# xmas_ornament_2019.net
KiCad netlist of a schematic drawn in EAGLE
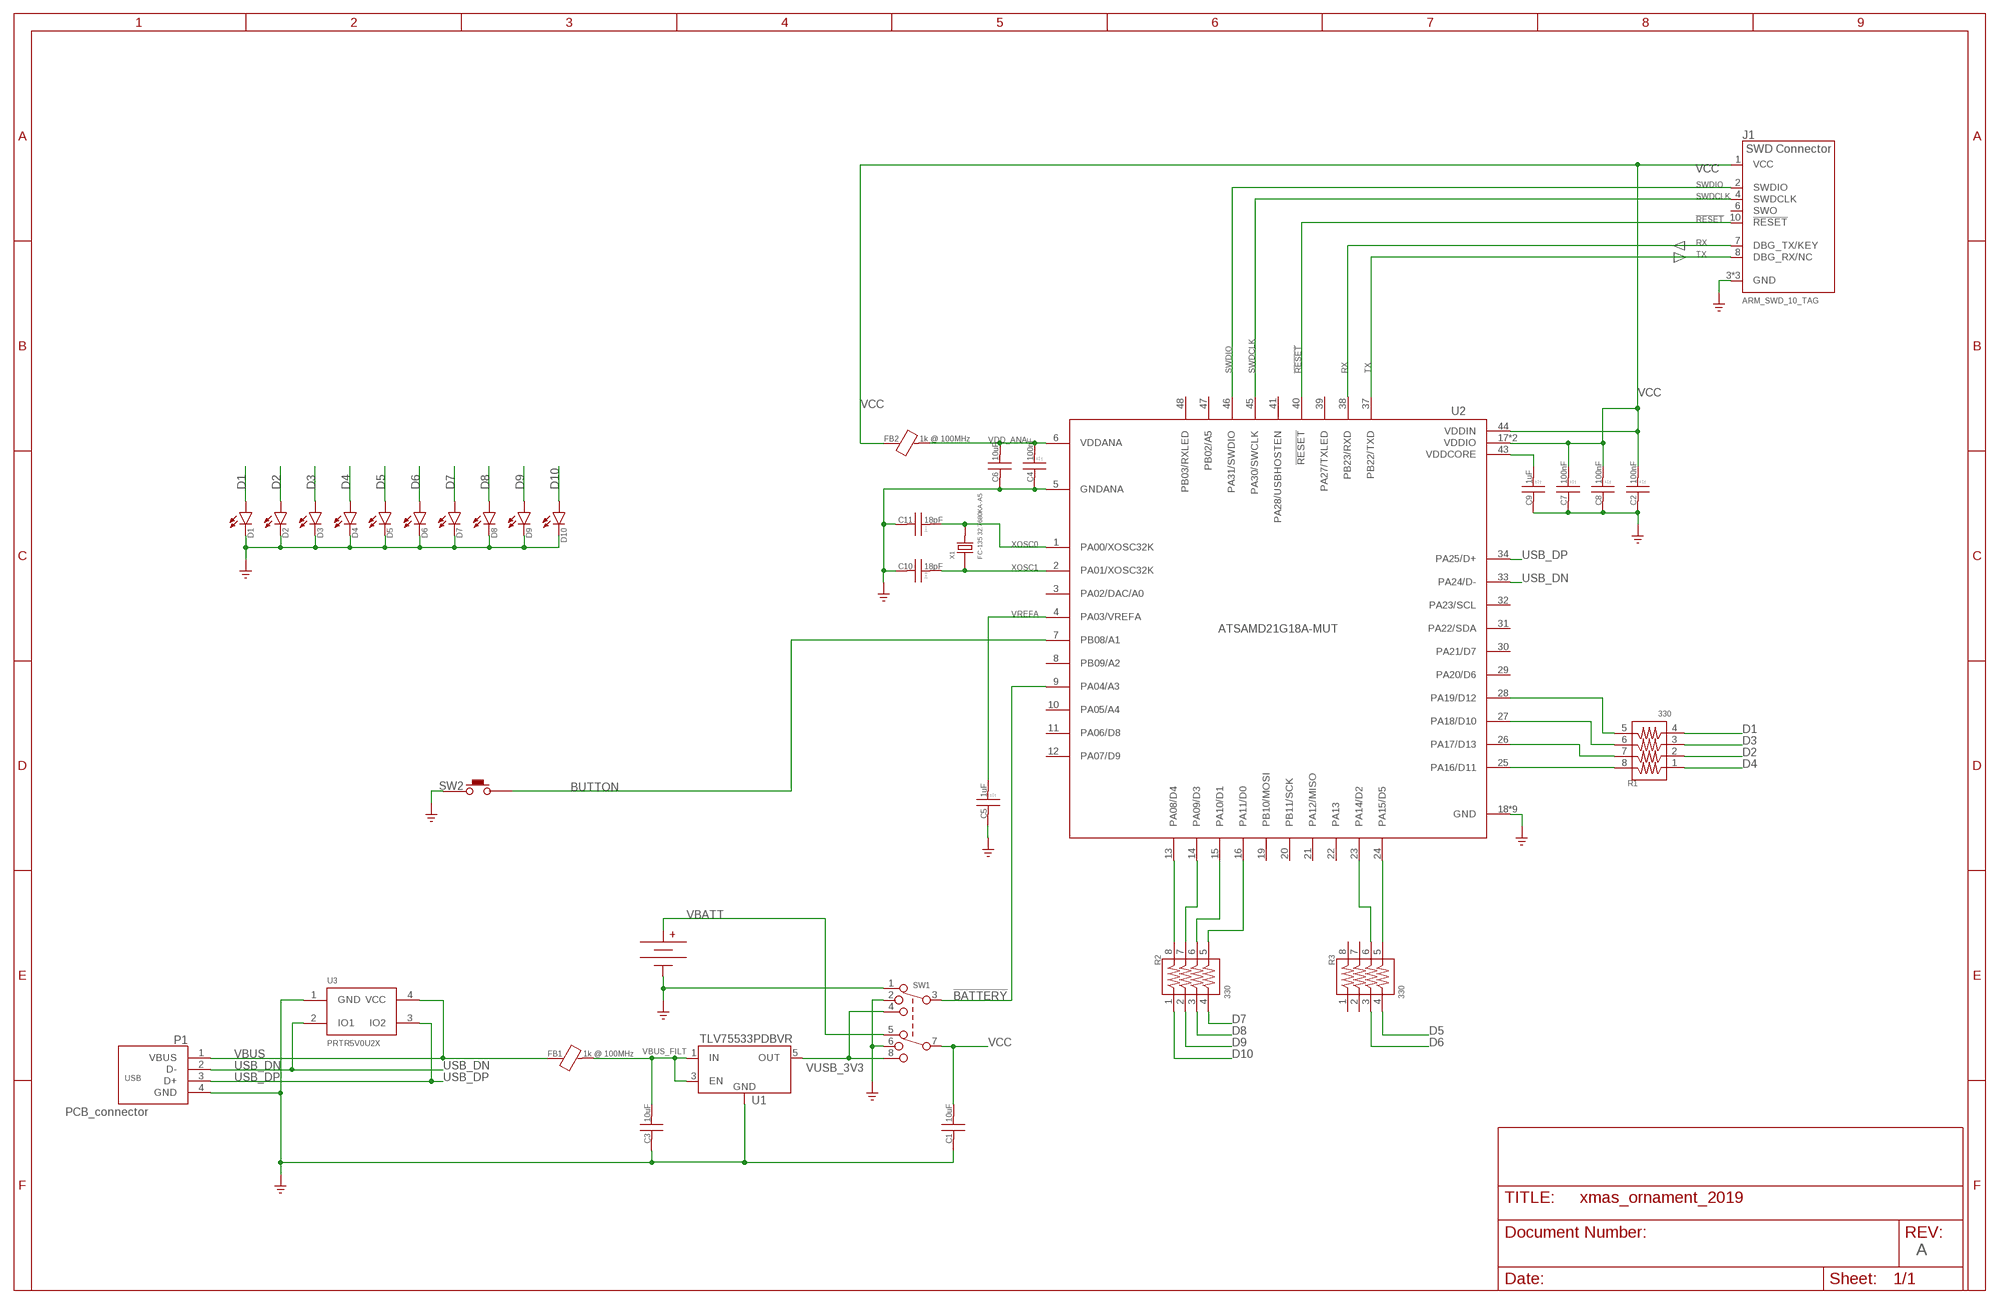
[diagram p0: schematic, sheet 1]

(export (version "E")
  (design (tool "Eeschema 10.0.6"))
  (components
    (comp (ref "C1")
      (value "10uF")
      (footprint "eagle-import:0805")
      (fields
        (field (name "DIELECTRIC") "X7R")
        (field (name "MPN") "JMK212AB7106KGHT")
        (field (name "TOLERANCE") "20%")
        (field (name "VOLTAGE") "6.3V")
      )
      (libsource (lib "eagle-import") (part "CAP_0805"))
    )
    (comp (ref "C2")
      (value "100nF")
      (footprint "eagle-import:0603")
      (fields
        (field (name "DIELECTRIC") "X5R")
        (field (name "MPN") "CC0603KRX7R9BB104")
        (field (name "TOLERANCE") "20%")
        (field (name "VOLTAGE") "50V")
      )
      (libsource (lib "eagle-import") (part "CAP_0603"))
    )
    (comp (ref "C3")
      (value "10uF")
      (footprint "eagle-import:0805")
      (fields
        (field (name "DIELECTRIC") "X7R")
        (field (name "MPN") "JMK212AB7106KGHT")
        (field (name "TOLERANCE") "20%")
        (field (name "VOLTAGE") "6.3V")
      )
      (libsource (lib "eagle-import") (part "CAP_0805"))
    )
    (comp (ref "C4")
      (value "100nF")
      (footprint "eagle-import:0603")
      (fields
        (field (name "DIELECTRIC") "X5R")
        (field (name "MPN") "CC0603KRX7R9BB104")
        (field (name "TOLERANCE") "20%")
        (field (name "VOLTAGE") "50V")
      )
      (libsource (lib "eagle-import") (part "CAP_0603"))
    )
    (comp (ref "C5")
      (value "1uF")
      (footprint "eagle-import:0603")
      (fields
        (field (name "DIELECTRIC") "X5R")
        (field (name "MPN") "CC0603KRX5R6BB105")
        (field (name "TOLERANCE") "20%")
        (field (name "VOLTAGE") "10V")
      )
      (libsource (lib "eagle-import") (part "CAP_0603"))
    )
    (comp (ref "C6")
      (value "10uF")
      (footprint "eagle-import:0805")
      (fields
        (field (name "DIELECTRIC") "X7R")
        (field (name "MPN") "JMK212AB7106KGHT")
        (field (name "TOLERANCE") "20%")
        (field (name "VOLTAGE") "6.3V")
      )
      (libsource (lib "eagle-import") (part "CAP_0805"))
    )
    (comp (ref "C7")
      (value "100nF")
      (footprint "eagle-import:0603")
      (fields
        (field (name "DIELECTRIC") "X5R")
        (field (name "MPN") "CC0603KRX7R9BB104")
        (field (name "TOLERANCE") "20%")
        (field (name "VOLTAGE") "50V")
      )
      (libsource (lib "eagle-import") (part "CAP_0603"))
    )
    (comp (ref "C8")
      (value "100nF")
      (footprint "eagle-import:0603")
      (fields
        (field (name "DIELECTRIC") "X5R")
        (field (name "MPN") "CC0603KRX7R9BB104")
        (field (name "TOLERANCE") "20%")
        (field (name "VOLTAGE") "50V")
      )
      (libsource (lib "eagle-import") (part "CAP_0603"))
    )
    (comp (ref "C9")
      (value "1uF")
      (footprint "eagle-import:0603")
      (fields
        (field (name "DIELECTRIC") "X5R")
        (field (name "MPN") "CC0603KRX5R6BB105")
        (field (name "TOLERANCE") "20%")
        (field (name "VOLTAGE") "10V")
      )
      (libsource (lib "eagle-import") (part "CAP_0603"))
    )
    (comp (ref "C10")
      (value "18pF")
      (footprint "eagle-import:0603")
      (fields
        (field (name "DIELECTRIC") "C0G")
        (field (name "MPN") "GRM1885C1H220JA01D")
        (field (name "TOLERANCE") "5%")
        (field (name "VOLTAGE") "50V")
      )
      (libsource (lib "eagle-import") (part "CAP_0603"))
    )
    (comp (ref "C11")
      (value "18pF")
      (footprint "eagle-import:0603")
      (fields
        (field (name "DIELECTRIC") "C0G")
        (field (name "MPN") "GRM1885C1H220JA01D")
        (field (name "TOLERANCE") "5%")
        (field (name "VOLTAGE") "50V")
      )
      (libsource (lib "eagle-import") (part "CAP_0603"))
    )
    (comp (ref "D1")
      (value "APT2012LSYCK/J3-PRV")
      (footprint "eagle-import:LED_0805_BREV")
      (libsource (lib "eagle-import") (part "LED0805_BREV"))
    )
    (comp (ref "D2")
      (value "APT2012LSYCK/J3-PRV")
      (footprint "eagle-import:LED_0805_BREV")
      (libsource (lib "eagle-import") (part "LED0805_BREV"))
    )
    (comp (ref "D3")
      (value "APT2012LSYCK/J3-PRV")
      (footprint "eagle-import:LED_0805_BREV")
      (libsource (lib "eagle-import") (part "LED0805_BREV"))
    )
    (comp (ref "D4")
      (value "APT2012LSYCK/J3-PRV")
      (footprint "eagle-import:LED_0805_BREV")
      (libsource (lib "eagle-import") (part "LED0805_BREV"))
    )
    (comp (ref "D5")
      (value "APT2012LSYCK/J3-PRV")
      (footprint "eagle-import:LED_0805_BREV")
      (libsource (lib "eagle-import") (part "LED0805_BREV"))
    )
    (comp (ref "D6")
      (value "APT2012LSYCK/J3-PRV")
      (footprint "eagle-import:LED_0805_BREV")
      (libsource (lib "eagle-import") (part "LED0805_BREV"))
    )
    (comp (ref "D7")
      (value "APT2012LSYCK/J3-PRV")
      (footprint "eagle-import:LED_0805_BREV")
      (libsource (lib "eagle-import") (part "LED0805_BREV"))
    )
    (comp (ref "D8")
      (value "APT2012LSYCK/J3-PRV")
      (footprint "eagle-import:LED_0805_BREV")
      (libsource (lib "eagle-import") (part "LED0805_BREV"))
    )
    (comp (ref "D9")
      (value "APT2012LSYCK/J3-PRV")
      (footprint "eagle-import:LED_0805_BREV")
      (libsource (lib "eagle-import") (part "LED0805_BREV"))
    )
    (comp (ref "D10")
      (value "APT2012LSYCK/J3-PRV")
      (footprint "eagle-import:LED_0805_BREV")
      (libsource (lib "eagle-import") (part "LED0805_BREV"))
    )
    (comp (ref "FB1")
      (value "1k @ 100MHz")
      (footprint "eagle-import:0603")
      (fields (field (name "MPN") "742792663"))
      (libsource (lib "eagle-import") (part "FERRITE_BEAD_0603"))
    )
    (comp (ref "FB2")
      (value "1k @ 100MHz")
      (footprint "eagle-import:0603")
      (fields (field (name "MPN") "742792663"))
      (libsource (lib "eagle-import") (part "FERRITE_BEAD_0603"))
    )
    (comp (ref "J1")
      (value "ARM_SWD_10_TAG")
      (footprint "eagle-import:TC2050-IDC-NL")
      (libsource (lib "eagle-import") (part "ARM_SWD_10_TAG"))
    )
    (comp (ref "J2")
      (value "BU2450-SM-JJ-GTR")
      (footprint "eagle-import:BU2450SM-JJ-GTR")
      (libsource (lib "eagle-import") (part "BATTERY_BU2450SM-JJ-G"))
    )
    (comp (ref "P1")
      (value "PCB_connector")
      (footprint "eagle-import:USB-A_PCB")
      (libsource (lib "eagle-import") (part "USB-4-PCB-A"))
    )
    (comp (ref "R1")
      (value "330")
      (footprint "eagle-import:1206X4")
      (fields (field (name "MPN") "EXB-38V331JV") (field (name "TOLERANCE") "5%"))
      (libsource (lib "eagle-import") (part "RESISTOR_4_1206"))
    )
    (comp (ref "R2")
      (value "330")
      (footprint "eagle-import:1206X4")
      (fields (field (name "MPN") "EXB-38V331JV") (field (name "TOLERANCE") "5%"))
      (libsource (lib "eagle-import") (part "RESISTOR_4_1206"))
    )
    (comp (ref "R3")
      (value "330")
      (footprint "eagle-import:1206X4")
      (fields (field (name "MPN") "EXB-38V331JV") (field (name "TOLERANCE") "5%"))
      (libsource (lib "eagle-import") (part "RESISTOR_4_1206"))
    )
    (comp (ref "SW1")
      (value "JS203011SCQN")
      (footprint "eagle-import:JS203011SCQN")
      (libsource (lib "eagle-import") (part "SWITCH-DP3T_JS203011SCQN"))
    )
    (comp (ref "SW2")
      (value "PTS645SM43SMTR92 LFS")
      (footprint "eagle-import:SWITCH_6MM")
      (libsource (lib "eagle-import") (part "SWITCH-SPST-NO"))
    )
    (comp (ref "U1")
      (value "TLV75533PDBVR")
      (footprint "eagle-import:SOT23-5")
      (libsource (lib "eagle-import") (part "VREG_FIXED+_ENTPS70960DBV"))
    )
    (comp (ref "U2")
      (value "ATSAMD21G18A-MUT")
      (footprint "eagle-import:QFN-48_GND")
      (libsource (lib "eagle-import") (part "SAMD21G18A-MUT"))
    )
    (comp (ref "U3")
      (value "PRTR5V0U2X")
      (footprint "eagle-import:SOT143B")
      (fields (field (name "MPN") "PRTR5V0U2X,215"))
      (libsource (lib "eagle-import") (part "PRTR5V0U2X"))
    )
    (comp (ref "X1")
      (value "FC-135 32.7680KA-A5")
      (footprint "eagle-import:XTAL_3.2X1.5")
      (libsource (lib "eagle-import") (part "XTAL-2_3.2X1.5"))
    )
  )
  (nets
    (net (code "1") (name "/BUTTON") (class "Default")
      (node (ref "SW2") (pin "1") (pinfunction "P$1_1") (pintype "bidirectional"))
      (node (ref "SW2") (pin "2") (pinfunction "P$1_2") (pintype "bidirectional"))
      (node (ref "U2") (pin "7") (pinfunction "PB08/A1_7") (pintype "bidirectional"))
    )
    (net (code "2") (name "/D1") (class "Default")
      (node (ref "D1") (pin "A") (pinfunction "A_A") (pintype "passive"))
      (node (ref "R1") (pin "4") (pinfunction "4A_4") (pintype "bidirectional"))
    )
    (net (code "3") (name "/D2") (class "Default")
      (node (ref "D2") (pin "A") (pinfunction "A_A") (pintype "passive"))
      (node (ref "R1") (pin "2") (pinfunction "2A_2") (pintype "bidirectional"))
    )
    (net (code "4") (name "/D3") (class "Default")
      (node (ref "D3") (pin "A") (pinfunction "A_A") (pintype "passive"))
      (node (ref "R1") (pin "3") (pinfunction "3A_3") (pintype "bidirectional"))
    )
    (net (code "5") (name "/D4") (class "Default")
      (node (ref "D4") (pin "A") (pinfunction "A_A") (pintype "passive"))
      (node (ref "R1") (pin "1") (pinfunction "1A_1") (pintype "bidirectional"))
    )
    (net (code "6") (name "/D5") (class "Default")
      (node (ref "D5") (pin "A") (pinfunction "A_A") (pintype "passive"))
      (node (ref "R3") (pin "4") (pinfunction "4A_4") (pintype "bidirectional"))
    )
    (net (code "7") (name "/D6") (class "Default")
      (node (ref "D6") (pin "A") (pinfunction "A_A") (pintype "passive"))
      (node (ref "R3") (pin "3") (pinfunction "3A_3") (pintype "bidirectional"))
    )
    (net (code "8") (name "/D7") (class "Default")
      (node (ref "D7") (pin "A") (pinfunction "A_A") (pintype "passive"))
      (node (ref "R2") (pin "4") (pinfunction "4A_4") (pintype "bidirectional"))
    )
    (net (code "9") (name "/D8") (class "Default")
      (node (ref "D8") (pin "A") (pinfunction "A_A") (pintype "passive"))
      (node (ref "R2") (pin "3") (pinfunction "3A_3") (pintype "bidirectional"))
    )
    (net (code "10") (name "/D9") (class "Default")
      (node (ref "D9") (pin "A") (pinfunction "A_A") (pintype "passive"))
      (node (ref "R2") (pin "2") (pinfunction "2A_2") (pintype "bidirectional"))
    )
    (net (code "11") (name "/D10") (class "Default")
      (node (ref "D10") (pin "A") (pinfunction "A_A") (pintype "passive"))
      (node (ref "R2") (pin "1") (pinfunction "1A_1") (pintype "bidirectional"))
    )
    (net (code "12") (name "/RX") (class "Default")
      (node (ref "J1") (pin "7") (pinfunction "DBG_TX/KEY_7") (pintype "bidirectional"))
      (node (ref "U2") (pin "38") (pinfunction "PB23/RXD_38") (pintype "bidirectional"))
    )
    (net (code "13") (name "/SWDCLK") (class "Default")
      (node (ref "J1") (pin "4") (pinfunction "SWDCLK_4") (pintype "bidirectional"))
      (node (ref "U2") (pin "45") (pinfunction "PA30/SWCLK_45") (pintype "bidirectional"))
    )
    (net (code "14") (name "/SWDIO") (class "Default")
      (node (ref "J1") (pin "2") (pinfunction "SWDIO_2") (pintype "bidirectional"))
      (node (ref "U2") (pin "46") (pinfunction "PA31/SWDIO_46") (pintype "bidirectional"))
    )
    (net (code "15") (name "/TX") (class "Default")
      (node (ref "J1") (pin "8") (pinfunction "DBG_RX/NC_8") (pintype "bidirectional"))
      (node (ref "U2") (pin "37") (pinfunction "PB22/TXD_37") (pintype "bidirectional"))
    )
    (net (code "16") (name "/USB_DN") (class "Default")
      (node (ref "P1") (pin "2") (pinfunction "D-_2") (pintype "bidirectional"))
      (node (ref "U2") (pin "33") (pinfunction "PA24/D-_33") (pintype "bidirectional"))
      (node (ref "U3") (pin "2") (pinfunction "IO1_2") (pintype "bidirectional"))
    )
    (net (code "17") (name "/USB_DP") (class "Default")
      (node (ref "P1") (pin "3") (pinfunction "D+_3") (pintype "bidirectional"))
      (node (ref "U2") (pin "34") (pinfunction "PA25/D+_34") (pintype "bidirectional"))
      (node (ref "U3") (pin "3") (pinfunction "IO2_3") (pintype "bidirectional"))
    )
    (net (code "18") (name "/VBATT") (class "Default")
      (node (ref "J2") (pin "+") (pinfunction "+_+") (pintype "bidirectional"))
      (node (ref "SW1") (pin "5") (pinfunction "B1_5") (pintype "bidirectional"))
    )
    (net (code "19") (name "/VBUS") (class "Default")
      (node (ref "FB1") (pin "1") (pinfunction "1_1") (pintype "bidirectional"))
      (node (ref "P1") (pin "1") (pinfunction "VBUS_1") (pintype "bidirectional"))
      (node (ref "U3") (pin "4") (pinfunction "VCC_4") (pintype "bidirectional"))
    )
    (net (code "20") (name "/VBUS_FILT") (class "Default")
      (node (ref "C3") (pin "2") (pinfunction "2_2") (pintype "bidirectional"))
      (node (ref "FB1") (pin "2") (pinfunction "2_2") (pintype "bidirectional"))
      (node (ref "U1") (pin "1") (pinfunction "IN_1") (pintype "bidirectional"))
      (node (ref "U1") (pin "3") (pinfunction "EN_3") (pintype "bidirectional"))
    )
    (net (code "21") (name "/VCC") (class "Default")
      (node (ref "C1") (pin "2") (pinfunction "2_2") (pintype "bidirectional"))
      (node (ref "C2") (pin "2") (pinfunction "2_2") (pintype "bidirectional"))
      (node (ref "C7") (pin "2") (pinfunction "2_2") (pintype "bidirectional"))
      (node (ref "C8") (pin "2") (pinfunction "2_2") (pintype "bidirectional"))
      (node (ref "FB2") (pin "1") (pinfunction "1_1") (pintype "bidirectional"))
      (node (ref "J1") (pin "1") (pinfunction "VCC_1") (pintype "bidirectional"))
      (node (ref "SW1") (pin "7") (pinfunction "B_COM_7") (pintype "bidirectional"))
      (node (ref "U2") (pin "17") (pinfunction "VDDIO_17") (pintype "bidirectional"))
      (node (ref "U2") (pin "36") (pinfunction "VDDIO_36") (pintype "bidirectional"))
      (node (ref "U2") (pin "44") (pinfunction "VDDIN_44") (pintype "bidirectional"))
    )
    (net (code "22") (name "/VDD_ANA") (class "Default")
      (node (ref "C4") (pin "2") (pinfunction "2_2") (pintype "bidirectional"))
      (node (ref "C6") (pin "2") (pinfunction "2_2") (pintype "bidirectional"))
      (node (ref "FB2") (pin "2") (pinfunction "2_2") (pintype "bidirectional"))
      (node (ref "U2") (pin "6") (pinfunction "VDDANA_6") (pintype "bidirectional"))
    )
    (net (code "23") (name "/VREFA") (class "Default")
      (node (ref "C5") (pin "2") (pinfunction "2_2") (pintype "bidirectional"))
      (node (ref "U2") (pin "4") (pinfunction "PA03/VREFA_4") (pintype "bidirectional"))
    )
    (net (code "24") (name "/VUSB_3V3") (class "Default")
      (node (ref "SW1") (pin "4") (pinfunction "A3_4") (pintype "bidirectional"))
      (node (ref "SW1") (pin "8") (pinfunction "B3_8") (pintype "bidirectional"))
      (node (ref "U1") (pin "5") (pinfunction "OUT_5") (pintype "bidirectional"))
    )
    (net (code "25") (name "/XOSC0") (class "Default")
      (node (ref "C11") (pin "2") (pinfunction "2_2") (pintype "bidirectional"))
      (node (ref "U2") (pin "1") (pinfunction "PA00/XOSC32K_1") (pintype "bidirectional"))
      (node (ref "X1") (pin "2") (pinfunction "2_2") (pintype "passive"))
    )
    (net (code "26") (name "/XOSC1") (class "Default")
      (node (ref "C10") (pin "2") (pinfunction "2_2") (pintype "bidirectional"))
      (node (ref "U2") (pin "2") (pinfunction "PA01/XOSC32K_2") (pintype "bidirectional"))
      (node (ref "X1") (pin "1") (pinfunction "1_1") (pintype "passive"))
    )
    (net (code "27") (name "/~{BATTERY}") (class "Default")
      (node (ref "SW1") (pin "3") (pinfunction "A_COM_3") (pintype "bidirectional"))
      (node (ref "U2") (pin "9") (pinfunction "PA04/A3_9") (pintype "bidirectional"))
    )
    (net (code "28") (name "/~{RESET}") (class "Default")
      (node (ref "J1") (pin "10") (pinfunction "~{RESET}_10") (pintype "bidirectional"))
      (node (ref "U2") (pin "40") (pinfunction "~{RESET}_40") (pintype "bidirectional"))
    )
    (net (code "29") (name "GND_EARTH") (class "Default")
      (node (ref "C1") (pin "1") (pinfunction "1_1") (pintype "bidirectional"))
      (node (ref "C10") (pin "1") (pinfunction "1_1") (pintype "bidirectional"))
      (node (ref "C11") (pin "1") (pinfunction "1_1") (pintype "bidirectional"))
      (node (ref "C2") (pin "1") (pinfunction "1_1") (pintype "bidirectional"))
      (node (ref "C3") (pin "1") (pinfunction "1_1") (pintype "bidirectional"))
      (node (ref "C4") (pin "1") (pinfunction "1_1") (pintype "bidirectional"))
      (node (ref "C5") (pin "1") (pinfunction "1_1") (pintype "bidirectional"))
      (node (ref "C6") (pin "1") (pinfunction "1_1") (pintype "bidirectional"))
      (node (ref "C7") (pin "1") (pinfunction "1_1") (pintype "bidirectional"))
      (node (ref "C8") (pin "1") (pinfunction "1_1") (pintype "bidirectional"))
      (node (ref "C9") (pin "1") (pinfunction "1_1") (pintype "bidirectional"))
      (node (ref "D1") (pin "C") (pinfunction "C_C") (pintype "passive"))
      (node (ref "D10") (pin "C") (pinfunction "C_C") (pintype "passive"))
      (node (ref "D2") (pin "C") (pinfunction "C_C") (pintype "passive"))
      (node (ref "D3") (pin "C") (pinfunction "C_C") (pintype "passive"))
      (node (ref "D4") (pin "C") (pinfunction "C_C") (pintype "passive"))
      (node (ref "D5") (pin "C") (pinfunction "C_C") (pintype "passive"))
      (node (ref "D6") (pin "C") (pinfunction "C_C") (pintype "passive"))
      (node (ref "D7") (pin "C") (pinfunction "C_C") (pintype "passive"))
      (node (ref "D8") (pin "C") (pinfunction "C_C") (pintype "passive"))
      (node (ref "D9") (pin "C") (pinfunction "C_C") (pintype "passive"))
      (node (ref "J1") (pin "3") (pinfunction "GND_3") (pintype "bidirectional"))
      (node (ref "J1") (pin "5") (pinfunction "GND_5") (pintype "bidirectional"))
      (node (ref "J1") (pin "9") (pinfunction "GND_9") (pintype "bidirectional"))
      (node (ref "J2") (pin "-") (pinfunction "-_-") (pintype "bidirectional"))
      (node (ref "P1") (pin "4") (pinfunction "GND_4") (pintype "bidirectional"))
      (node (ref "SW1") (pin "1") (pinfunction "A1_1") (pintype "bidirectional"))
      (node (ref "SW1") (pin "2") (pinfunction "A2_2") (pintype "bidirectional"))
      (node (ref "SW1") (pin "6") (pinfunction "B2_6") (pintype "bidirectional"))
      (node (ref "SW2") (pin "3") (pinfunction "P$2_3") (pintype "bidirectional"))
      (node (ref "SW2") (pin "4") (pinfunction "P$2_4") (pintype "bidirectional"))
      (node (ref "U1") (pin "2") (pinfunction "GND_2") (pintype "bidirectional"))
      (node (ref "U2") (pin "18") (pinfunction "GND_18") (pintype "bidirectional"))
      (node (ref "U2") (pin "35") (pinfunction "GND_35") (pintype "bidirectional"))
      (node (ref "U2") (pin "42") (pinfunction "GND_42") (pintype "bidirectional"))
      (node (ref "U2") (pin "5") (pinfunction "GNDANA_5") (pintype "bidirectional"))
      (node (ref "U2") (pin "GND") (pinfunction "GND_GND") (pintype "bidirectional"))
      (node (ref "U2") (pin "GND@A") (pinfunction "GND_GND@A") (pintype "bidirectional"))
      (node (ref "U2") (pin "GND@A1") (pinfunction "GND_GND@A1") (pintype "bidirectional"))
      (node (ref "U2") (pin "GND@A2") (pinfunction "GND_GND@A2") (pintype "bidirectional"))
      (node (ref "U2") (pin "GND@A3") (pinfunction "GND_GND@A3") (pintype "bidirectional"))
      (node (ref "U2") (pin "GND@A4") (pinfunction "GND_GND@A4") (pintype "bidirectional"))
      (node (ref "U3") (pin "1") (pinfunction "GND_1") (pintype "bidirectional"))
    )
    (net (code "30") (name "Net-(R1-1B)") (class "Default")
      (node (ref "R1") (pin "8") (pinfunction "1B_8") (pintype "bidirectional"))
      (node (ref "U2") (pin "25") (pinfunction "PA16/D11_25") (pintype "bidirectional"))
    )
    (net (code "31") (name "Net-(R1-2B)") (class "Default")
      (node (ref "R1") (pin "7") (pinfunction "2B_7") (pintype "bidirectional"))
      (node (ref "U2") (pin "26") (pinfunction "PA17/D13_26") (pintype "bidirectional"))
    )
    (net (code "32") (name "Net-(R1-3B)") (class "Default")
      (node (ref "R1") (pin "6") (pinfunction "3B_6") (pintype "bidirectional"))
      (node (ref "U2") (pin "27") (pinfunction "PA18/D10_27") (pintype "bidirectional"))
    )
    (net (code "33") (name "Net-(R1-4B)") (class "Default")
      (node (ref "R1") (pin "5") (pinfunction "4B_5") (pintype "bidirectional"))
      (node (ref "U2") (pin "28") (pinfunction "PA19/D12_28") (pintype "bidirectional"))
    )
    (net (code "34") (name "Net-(R2-1B)") (class "Default")
      (node (ref "R2") (pin "8") (pinfunction "1B_8") (pintype "bidirectional"))
      (node (ref "U2") (pin "13") (pinfunction "PA08/D4_13") (pintype "bidirectional"))
    )
    (net (code "35") (name "Net-(R2-2B)") (class "Default")
      (node (ref "R2") (pin "7") (pinfunction "2B_7") (pintype "bidirectional"))
      (node (ref "U2") (pin "14") (pinfunction "PA09/D3_14") (pintype "bidirectional"))
    )
    (net (code "36") (name "Net-(R2-3B)") (class "Default")
      (node (ref "R2") (pin "6") (pinfunction "3B_6") (pintype "bidirectional"))
      (node (ref "U2") (pin "15") (pinfunction "PA10/D1_15") (pintype "bidirectional"))
    )
    (net (code "37") (name "Net-(R2-4B)") (class "Default")
      (node (ref "R2") (pin "5") (pinfunction "4B_5") (pintype "bidirectional"))
      (node (ref "U2") (pin "16") (pinfunction "PA11/D0_16") (pintype "bidirectional"))
    )
    (net (code "38") (name "Net-(R3-3B)") (class "Default")
      (node (ref "R3") (pin "6") (pinfunction "3B_6") (pintype "bidirectional"))
      (node (ref "U2") (pin "23") (pinfunction "PA14/D2_23") (pintype "bidirectional"))
    )
    (net (code "39") (name "Net-(R3-4B)") (class "Default")
      (node (ref "R3") (pin "5") (pinfunction "4B_5") (pintype "bidirectional"))
      (node (ref "U2") (pin "24") (pinfunction "PA15/D5_24") (pintype "bidirectional"))
    )
    (net (code "40") (name "Net-(U2-VDDCORE)") (class "Default")
      (node (ref "C9") (pin "2") (pinfunction "2_2") (pintype "bidirectional"))
      (node (ref "U2") (pin "43") (pinfunction "VDDCORE_43") (pintype "bidirectional"))
    )
    (net (code "41") (name "unconnected-(J1-SWO-Pad6)") (class "Default")
      (node (ref "J1") (pin "6") (pinfunction "SWO_6") (pintype "bidirectional"))
    )
    (net (code "42") (name "unconnected-(R3-1A-Pad1)") (class "Default")
      (node (ref "R3") (pin "1") (pinfunction "1A_1") (pintype "bidirectional"))
    )
    (net (code "43") (name "unconnected-(R3-1B-Pad8)") (class "Default")
      (node (ref "R3") (pin "8") (pinfunction "1B_8") (pintype "bidirectional"))
    )
    (net (code "44") (name "unconnected-(R3-2A-Pad2)") (class "Default")
      (node (ref "R3") (pin "2") (pinfunction "2A_2") (pintype "bidirectional"))
    )
    (net (code "45") (name "unconnected-(R3-2B-Pad7)") (class "Default")
      (node (ref "R3") (pin "7") (pinfunction "2B_7") (pintype "bidirectional"))
    )
    (net (code "46") (name "unconnected-(U2-PA02{slash}DAC{slash}A0-Pad3)") (class "Default")
      (node (ref "U2") (pin "3") (pinfunction "PA02/DAC/A0_3") (pintype "bidirectional"))
    )
    (net (code "47") (name "unconnected-(U2-PA05{slash}A4-Pad10)") (class "Default")
      (node (ref "U2") (pin "10") (pinfunction "PA05/A4_10") (pintype "bidirectional"))
    )
    (net (code "48") (name "unconnected-(U2-PA06{slash}D8-Pad11)") (class "Default")
      (node (ref "U2") (pin "11") (pinfunction "PA06/D8_11") (pintype "bidirectional"))
    )
    (net (code "49") (name "unconnected-(U2-PA07{slash}D9-Pad12)") (class "Default")
      (node (ref "U2") (pin "12") (pinfunction "PA07/D9_12") (pintype "bidirectional"))
    )
    (net (code "50") (name "unconnected-(U2-PA12{slash}MISO-Pad21)") (class "Default")
      (node (ref "U2") (pin "21") (pinfunction "PA12/MISO_21") (pintype "bidirectional"))
    )
    (net (code "51") (name "unconnected-(U2-PA13-Pad22)") (class "Default")
      (node (ref "U2") (pin "22") (pinfunction "PA13_22") (pintype "bidirectional"))
    )
    (net (code "52") (name "unconnected-(U2-PA20{slash}D6-Pad29)") (class "Default")
      (node (ref "U2") (pin "29") (pinfunction "PA20/D6_29") (pintype "bidirectional"))
    )
    (net (code "53") (name "unconnected-(U2-PA21{slash}D7-Pad30)") (class "Default")
      (node (ref "U2") (pin "30") (pinfunction "PA21/D7_30") (pintype "bidirectional"))
    )
    (net (code "54") (name "unconnected-(U2-PA22{slash}SDA-Pad31)") (class "Default")
      (node (ref "U2") (pin "31") (pinfunction "PA22/SDA_31") (pintype "bidirectional"))
    )
    (net (code "55") (name "unconnected-(U2-PA23{slash}SCL-Pad32)") (class "Default")
      (node (ref "U2") (pin "32") (pinfunction "PA23/SCL_32") (pintype "bidirectional"))
    )
    (net (code "56") (name "unconnected-(U2-PA27{slash}TXLED-Pad39)") (class "Default")
      (node (ref "U2") (pin "39") (pinfunction "PA27/TXLED_39") (pintype "bidirectional"))
    )
    (net (code "57") (name "unconnected-(U2-PA28{slash}USBHOSTEN-Pad41)") (class "Default")
      (node (ref "U2") (pin "41") (pinfunction "PA28/USBHOSTEN_41") (pintype "bidirectional"))
    )
    (net (code "58") (name "unconnected-(U2-PB02{slash}A5-Pad47)") (class "Default")
      (node (ref "U2") (pin "47") (pinfunction "PB02/A5_47") (pintype "bidirectional"))
    )
    (net (code "59") (name "unconnected-(U2-PB03{slash}RXLED-Pad48)") (class "Default")
      (node (ref "U2") (pin "48") (pinfunction "PB03/RXLED_48") (pintype "bidirectional"))
    )
    (net (code "60") (name "unconnected-(U2-PB09{slash}A2-Pad8)") (class "Default")
      (node (ref "U2") (pin "8") (pinfunction "PB09/A2_8") (pintype "bidirectional"))
    )
    (net (code "61") (name "unconnected-(U2-PB10{slash}MOSI-Pad19)") (class "Default")
      (node (ref "U2") (pin "19") (pinfunction "PB10/MOSI_19") (pintype "bidirectional"))
    )
    (net (code "62") (name "unconnected-(U2-PB11{slash}SCK-Pad20)") (class "Default")
      (node (ref "U2") (pin "20") (pinfunction "PB11/SCK_20") (pintype "bidirectional"))
    )
  )
)
